# adafruid_breakout.net
KiCad netlist of a schematic drawn in EAGLE
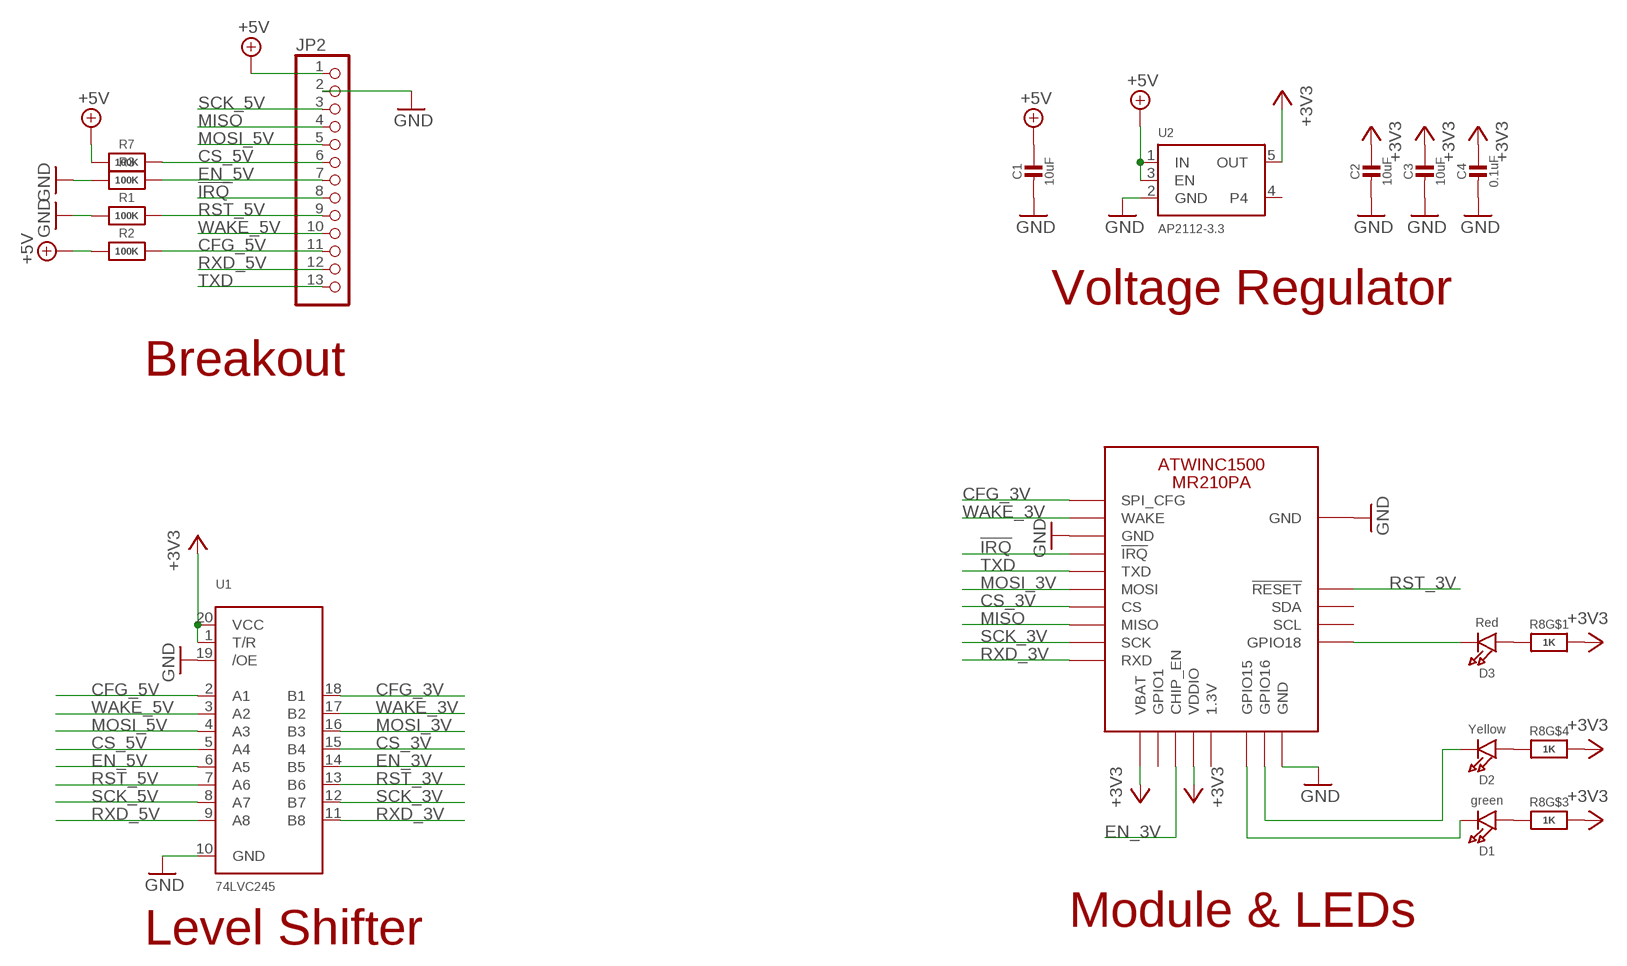
[diagram p0: schematic, sheet 1]

(export (version "E")
  (design (tool "Eeschema 10.0.6"))
  (components
    (comp (ref "C1")
      (value "10uF")
      (footprint "eagle-import:0805-NO")
      (libsource (lib "eagle-import") (part "CAP_CERAMIC0805-NOOUTLINE"))
    )
    (comp (ref "C2")
      (value "10uF")
      (footprint "eagle-import:0805_10MGAP")
      (libsource (lib "eagle-import") (part "CAP_CERAMIC0805_10MGAP"))
    )
    (comp (ref "C3")
      (value "10uF")
      (footprint "eagle-import:0805-NO")
      (libsource (lib "eagle-import") (part "CAP_CERAMIC0805-NOOUTLINE"))
    )
    (comp (ref "C4")
      (value "0.1uF")
      (footprint "eagle-import:0805-NO")
      (libsource (lib "eagle-import") (part "CAP_CERAMIC0805-NOOUTLINE"))
    )
    (comp (ref "D1")
      (value "green")
      (footprint "eagle-import:CHIPLED_0805_NOOUTLINE")
      (libsource (lib "eagle-import") (part "LED0805_NOOUTLINE"))
    )
    (comp (ref "D2")
      (value "Yellow")
      (footprint "eagle-import:CHIPLED_0805_NOOUTLINE")
      (libsource (lib "eagle-import") (part "LED0805_NOOUTLINE"))
    )
    (comp (ref "D3")
      (value "Red")
      (footprint "eagle-import:CHIPLED_0805_NOOUTLINE")
      (libsource (lib "eagle-import") (part "LED0805_NOOUTLINE"))
    )
    (comp (ref "JP2")
      (value "HEADER-1X13")
      (footprint "eagle-import:1X13_ROUND_70")
      (libsource (lib "eagle-import") (part "HEADER-1X13"))
    )
    (comp (ref "R1")
      (value "100K")
      (footprint "eagle-import:0805-NO")
      (libsource (lib "eagle-import") (part "RESISTOR0805_NOOUTLINE"))
    )
    (comp (ref "R2")
      (value "100K")
      (footprint "eagle-import:0805-NO")
      (libsource (lib "eagle-import") (part "RESISTOR0805_NOOUTLINE"))
    )
    (comp (ref "R3")
      (value "100K")
      (footprint "eagle-import:_0805MP")
      (libsource (lib "eagle-import") (part "RESISTOR_0805MP"))
    )
    (comp (ref "R7")
      (value "100K")
      (footprint "eagle-import:_0805MP")
      (libsource (lib "eagle-import") (part "RESISTOR_0805MP"))
    )
    (comp (ref "R8")
      (value "1K")
      (footprint "eagle-import:RESPACK_4X0603")
      (libsource (lib "eagle-import") (part "RESISTOR_4PACK"))
    )
    (comp (ref "U$1")
      (value "ATWINC1500_MR210PB")
      (footprint "eagle-import:ATWINC1500_MR210PA")
      (libsource (lib "eagle-import") (part "ATWINC1500_MR210PA"))
    )
    (comp (ref "U1")
      (value "74LVC245")
      (footprint "eagle-import:TSSOP20")
      (libsource (lib "eagle-import") (part "74LCX245"))
    )
    (comp (ref "U2")
      (value "AP2112-3.3")
      (footprint "eagle-import:SOT23-5")
      (libsource (lib "eagle-import") (part "VREG_SOT23-5"))
    )
  )
  (nets
    (net (code "1") (name "+3V3") (class "Default")
      (node (ref "C2") (pin "1") (pinfunction "1_1") (pintype "passive"))
      (node (ref "C3") (pin "1") (pinfunction "1_1") (pintype "passive"))
      (node (ref "C4") (pin "1") (pinfunction "1_1") (pintype "passive"))
      (node (ref "R8") (pin "5") (pinfunction "2_5") (pintype "passive"))
      (node (ref "R8") (pin "6") (pinfunction "2_6") (pintype "passive"))
      (node (ref "R8") (pin "8") (pinfunction "2_8") (pintype "passive"))
      (node (ref "U$1") (pin "J20") (pinfunction "VBAT_J20") (pintype "power_in"))
      (node (ref "U$1") (pin "J23") (pinfunction "VDDIO_J23") (pintype "power_in"))
      (node (ref "U1") (pin "1") (pinfunction "T/R_1") (pintype "bidirectional"))
      (node (ref "U1") (pin "20") (pinfunction "VCC_20") (pintype "bidirectional"))
      (node (ref "U2") (pin "5") (pinfunction "OUT_5") (pintype "power_in"))
    )
    (net (code "2") (name "+5V") (class "Default")
      (node (ref "C1") (pin "1") (pinfunction "1_1") (pintype "passive"))
      (node (ref "JP2") (pin "1") (pinfunction "1_1") (pintype "passive"))
      (node (ref "R2") (pin "1") (pinfunction "1_1") (pintype "passive"))
      (node (ref "R7") (pin "1") (pinfunction "1_1") (pintype "passive"))
      (node (ref "U2") (pin "1") (pinfunction "IN_1") (pintype "power_in"))
      (node (ref "U2") (pin "3") (pinfunction "EN_3") (pintype "input"))
    )
    (net (code "3") (name "/CFG_3V") (class "Default")
      (node (ref "U$1") (pin "J10") (pinfunction "SPI_CFG_J10") (pintype "input"))
      (node (ref "U1") (pin "18") (pinfunction "B1_18") (pintype "bidirectional"))
    )
    (net (code "4") (name "/CFG_5V") (class "Default")
      (node (ref "JP2") (pin "11") (pinfunction "11_11") (pintype "passive"))
      (node (ref "R2") (pin "2") (pinfunction "2_2") (pintype "passive"))
      (node (ref "U1") (pin "2") (pinfunction "A1_2") (pintype "bidirectional"))
    )
    (net (code "5") (name "/CS_3V") (class "Default")
      (node (ref "U$1") (pin "J16") (pinfunction "CS_J16") (pintype "input"))
      (node (ref "U1") (pin "15") (pinfunction "B4_15") (pintype "bidirectional"))
    )
    (net (code "6") (name "/CS_5V") (class "Default")
      (node (ref "JP2") (pin "6") (pinfunction "6_6") (pintype "passive"))
      (node (ref "R7") (pin "2") (pinfunction "2_2") (pintype "passive"))
      (node (ref "U1") (pin "5") (pinfunction "A4_5") (pintype "bidirectional"))
    )
    (net (code "7") (name "/EN_3V") (class "Default")
      (node (ref "U$1") (pin "J22") (pinfunction "CHIP_EN_J22") (pintype "input"))
      (node (ref "U1") (pin "14") (pinfunction "B5_14") (pintype "bidirectional"))
    )
    (net (code "8") (name "/EN_5V") (class "Default")
      (node (ref "JP2") (pin "7") (pinfunction "7_7") (pintype "passive"))
      (node (ref "R3") (pin "2") (pinfunction "2_2") (pintype "passive"))
      (node (ref "U1") (pin "6") (pinfunction "A5_6") (pintype "bidirectional"))
    )
    (net (code "9") (name "/MISO") (class "Default")
      (node (ref "JP2") (pin "4") (pinfunction "4_4") (pintype "passive"))
      (node (ref "U$1") (pin "J17") (pinfunction "MISO_J17") (pintype "output"))
    )
    (net (code "10") (name "/MOSI_3V") (class "Default")
      (node (ref "U$1") (pin "J15") (pinfunction "MOSI_J15") (pintype "input"))
      (node (ref "U1") (pin "16") (pinfunction "B3_16") (pintype "bidirectional"))
    )
    (net (code "11") (name "/MOSI_5V") (class "Default")
      (node (ref "JP2") (pin "5") (pinfunction "5_5") (pintype "passive"))
      (node (ref "U1") (pin "4") (pinfunction "A3_4") (pintype "bidirectional"))
    )
    (net (code "12") (name "/RST_3V") (class "Default")
      (node (ref "U$1") (pin "J4") (pinfunction "~{RESET}_J4") (pintype "input"))
      (node (ref "U1") (pin "13") (pinfunction "B6_13") (pintype "bidirectional"))
    )
    (net (code "13") (name "/RST_5V") (class "Default")
      (node (ref "JP2") (pin "9") (pinfunction "9_9") (pintype "passive"))
      (node (ref "R1") (pin "2") (pinfunction "2_2") (pintype "passive"))
      (node (ref "U1") (pin "7") (pinfunction "A6_7") (pintype "bidirectional"))
    )
    (net (code "14") (name "/RXD_3V") (class "Default")
      (node (ref "U$1") (pin "J19") (pinfunction "RXD_J19") (pintype "input"))
      (node (ref "U1") (pin "11") (pinfunction "B8_11") (pintype "bidirectional"))
    )
    (net (code "15") (name "/RXD_5V") (class "Default")
      (node (ref "JP2") (pin "12") (pinfunction "12_12") (pintype "passive"))
      (node (ref "U1") (pin "9") (pinfunction "A8_9") (pintype "bidirectional"))
    )
    (net (code "16") (name "/SCK_3V") (class "Default")
      (node (ref "U$1") (pin "J18") (pinfunction "SCK_J18") (pintype "input"))
      (node (ref "U1") (pin "12") (pinfunction "B7_12") (pintype "bidirectional"))
    )
    (net (code "17") (name "/SCK_5V") (class "Default")
      (node (ref "JP2") (pin "3") (pinfunction "3_3") (pintype "passive"))
      (node (ref "U1") (pin "8") (pinfunction "A7_8") (pintype "bidirectional"))
    )
    (net (code "18") (name "/TXD") (class "Default")
      (node (ref "JP2") (pin "13") (pinfunction "13_13") (pintype "passive"))
      (node (ref "U$1") (pin "J14") (pinfunction "TXD_J14") (pintype "output"))
    )
    (net (code "19") (name "/WAKE_3V") (class "Default")
      (node (ref "U$1") (pin "J11") (pinfunction "WAKE_J11") (pintype "input"))
      (node (ref "U1") (pin "17") (pinfunction "B2_17") (pintype "bidirectional"))
    )
    (net (code "20") (name "/WAKE_5V") (class "Default")
      (node (ref "JP2") (pin "10") (pinfunction "10_10") (pintype "passive"))
      (node (ref "U1") (pin "3") (pinfunction "A2_3") (pintype "bidirectional"))
    )
    (net (code "21") (name "/~{IRQ}") (class "Default")
      (node (ref "JP2") (pin "8") (pinfunction "8_8") (pintype "passive"))
      (node (ref "U$1") (pin "J13") (pinfunction "~{IRQ}_J13") (pintype "output"))
    )
    (net (code "22") (name "GND") (class "Default")
      (node (ref "C1") (pin "2") (pinfunction "2_2") (pintype "passive"))
      (node (ref "C2") (pin "2") (pinfunction "2_2") (pintype "passive"))
      (node (ref "C3") (pin "2") (pinfunction "2_2") (pintype "passive"))
      (node (ref "C4") (pin "2") (pinfunction "2_2") (pintype "passive"))
      (node (ref "JP2") (pin "2") (pinfunction "2_2") (pintype "passive"))
      (node (ref "R1") (pin "1") (pinfunction "1_1") (pintype "passive"))
      (node (ref "R3") (pin "1") (pinfunction "1_1") (pintype "passive"))
      (node (ref "U$1") (pin "J12") (pinfunction "GND_J12") (pintype "power_in"))
      (node (ref "U$1") (pin "J28") (pinfunction "GND_J28") (pintype "power_in"))
      (node (ref "U$1") (pin "J9") (pinfunction "GND_J9") (pintype "bidirectional"))
      (node (ref "U$1") (pin "MTGND") (pinfunction "GND_MTGND") (pintype "power_in"))
      (node (ref "U1") (pin "10") (pinfunction "GND_10") (pintype "bidirectional"))
      (node (ref "U1") (pin "19") (pinfunction "/OE_19") (pintype "bidirectional"))
      (node (ref "U2") (pin "2") (pinfunction "GND_2") (pintype "power_in"))
    )
    (net (code "23") (name "Net-(D3-PadA)") (class "Default")
      (node (ref "D3") (pin "A") (pinfunction "A_A") (pintype "passive"))
      (node (ref "R8") (pin "1") (pinfunction "1_1") (pintype "passive"))
    )
    (net (code "24") (name "Net-(R8C-1)") (class "Default")
      (node (ref "D1") (pin "A") (pinfunction "A_A") (pintype "passive"))
      (node (ref "R8") (pin "3") (pinfunction "1_3") (pintype "passive"))
    )
    (net (code "25") (name "Net-(R8D-1)") (class "Default")
      (node (ref "D2") (pin "A") (pinfunction "A_A") (pintype "passive"))
      (node (ref "R8") (pin "4") (pinfunction "1_4") (pintype "passive"))
    )
    (net (code "26") (name "Net-(U$1-GPIO15)") (class "Default")
      (node (ref "D1") (pin "C") (pinfunction "C_C") (pintype "passive"))
      (node (ref "U$1") (pin "J26") (pinfunction "GPIO15_J26") (pintype "bidirectional"))
    )
    (net (code "27") (name "Net-(U$1-GPIO16)") (class "Default")
      (node (ref "D2") (pin "C") (pinfunction "C_C") (pintype "passive"))
      (node (ref "U$1") (pin "J27") (pinfunction "GPIO16_J27") (pintype "bidirectional"))
    )
    (net (code "28") (name "Net-(U$1-GPIO18)") (class "Default")
      (node (ref "D3") (pin "C") (pinfunction "C_C") (pintype "passive"))
      (node (ref "U$1") (pin "J1") (pinfunction "GPIO18_J1") (pintype "bidirectional"))
    )
    (net (code "29") (name "unconnected-(U$1-1.3V-PadJ24)") (class "Default")
      (node (ref "U$1") (pin "J24") (pinfunction "1.3V_J24") (pintype "passive"))
    )
    (net (code "30") (name "unconnected-(U$1-GPIO1-PadJ21)") (class "Default")
      (node (ref "U$1") (pin "J21") (pinfunction "GPIO1_J21") (pintype "bidirectional"))
    )
    (net (code "31") (name "unconnected-(U$1-SCL-PadJ2)") (class "Default")
      (node (ref "U$1") (pin "J2") (pinfunction "SCL_J2") (pintype "bidirectional"))
    )
    (net (code "32") (name "unconnected-(U$1-SDA-PadJ3)") (class "Default")
      (node (ref "U$1") (pin "J3") (pinfunction "SDA_J3") (pintype "bidirectional"))
    )
    (net (code "33") (name "unconnected-(U2-P4-Pad4)") (class "Default")
      (node (ref "U2") (pin "4") (pinfunction "P4_4") (pintype "bidirectional"))
    )
  )
)
